# EN-C200_RA0_PWR.net
KiCad netlist of a schematic drawn in Altium Designer
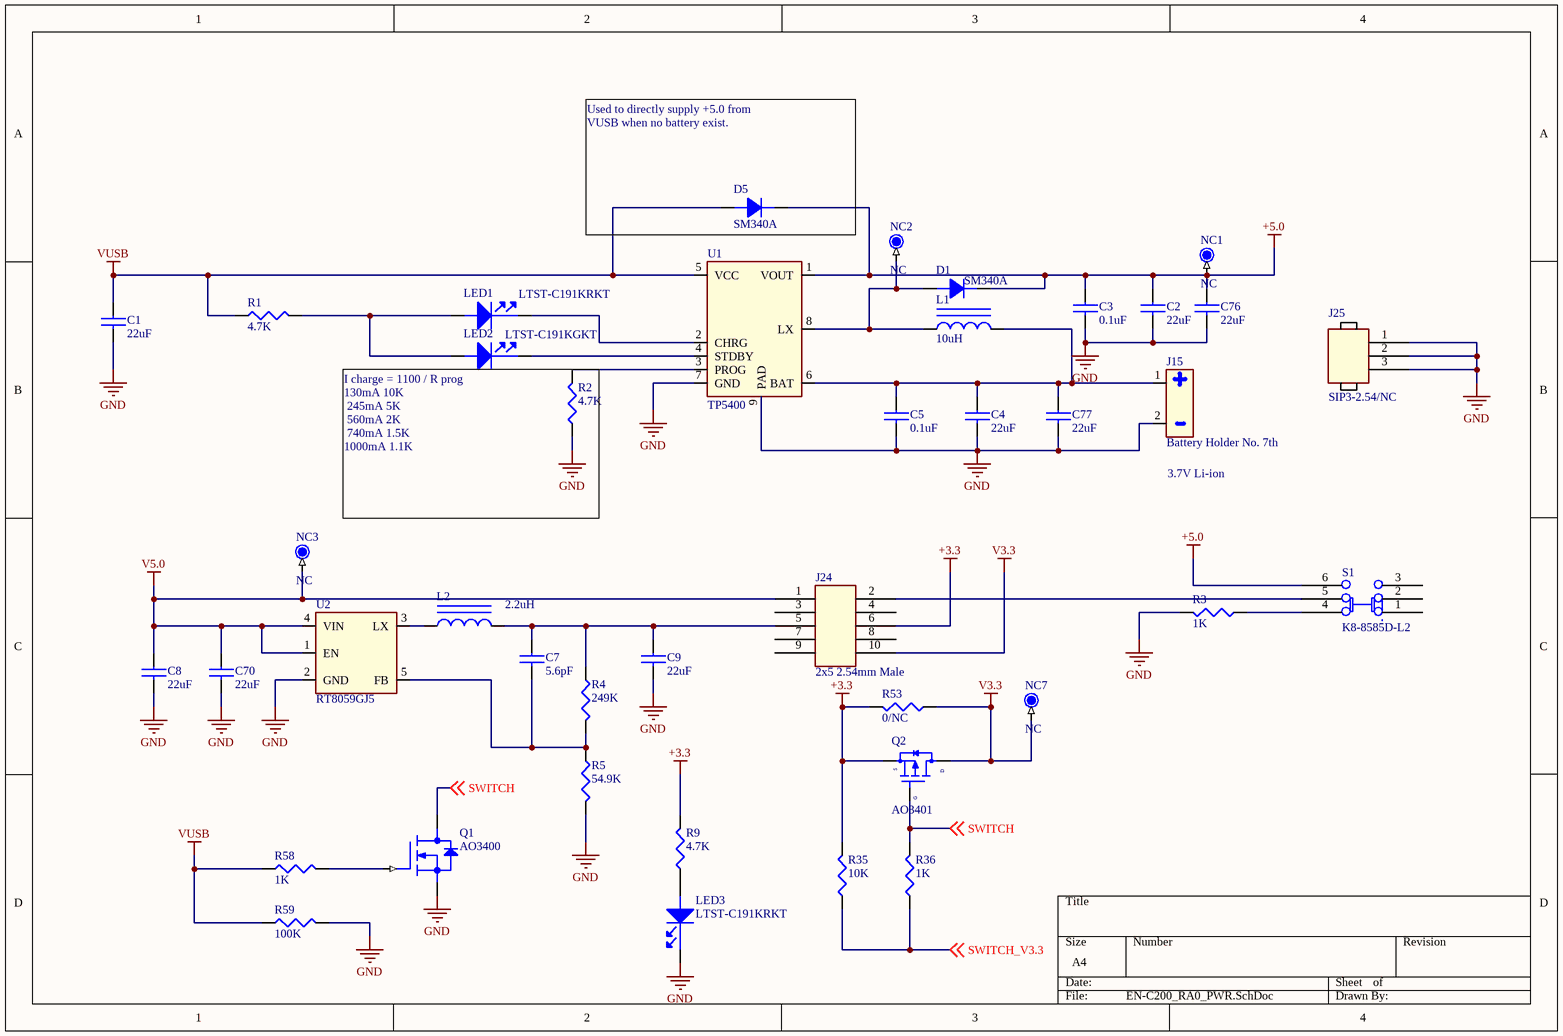
[diagram p0: EN-C200_RA0_PWR.SchDoc]

(export (version "E")
  (design (tool "Eeschema 10.0.6"))
  (components
    (comp (ref "C1") (value "22uF") (footprint "SC0805") (libsource (lib "EN-C200_RA0") (part "CAP NP")))
    (comp (ref "C2") (value "22uF") (footprint "SC0805") (libsource (lib "EN-C200_RA0") (part "CAP NP")))
    (comp (ref "C3") (value "0.1uF") (footprint "SC0603") (libsource (lib "EN-C200_RA0") (part "CAP NP")))
    (comp (ref "C4") (value "22uF") (footprint "SC0805") (libsource (lib "EN-C200_RA0") (part "CAP NP")))
    (comp (ref "C5") (value "0.1uF") (footprint "SC0603") (libsource (lib "EN-C200_RA0") (part "CAP NP")))
    (comp (ref "C7") (value "5.6pF") (footprint "SC0603") (libsource (lib "EN-C200_RA0") (part "CAP NP")))
    (comp (ref "C8") (value "22uF") (footprint "SC0805") (libsource (lib "EN-C200_RA0") (part "CAP NP")))
    (comp (ref "C9") (value "22uF") (footprint "SC0805") (libsource (lib "EN-C200_RA0") (part "CAP NP")))
    (comp (ref "C70") (value "22uF") (footprint "SC0805") (libsource (lib "EN-C200_RA0") (part "CAP NP")))
    (comp (ref "C76") (value "22uF") (footprint "SC0805") (libsource (lib "EN-C200_RA0") (part "CAP NP")))
    (comp (ref "C77") (value "22uF") (footprint "SC0805") (libsource (lib "EN-C200_RA0") (part "CAP NP")))
    (comp (ref "D1") (value "SM340A") (footprint "SD1714") (libsource (lib "EN-C200_RA0") (part "DIODE")))
    (comp (ref "D5") (value "SM340A") (footprint "SD1714") (libsource (lib "EN-C200_RA0") (part "DIODE")))
    (comp (ref "J15")
      (value "Battery Holder No. 7th")
      (footprint "BX0034")
      (libsource (lib "EN-C200_RA0") (part "BX0034"))
    )
    (comp (ref "J24")
      (value "2x5 2.54mm Male")
      (footprint "SIP-2X5P-100")
      (libsource (lib "EN-C200_RA0") (part "CON10A"))
    )
    (comp (ref "J25")
      (value "SIP3-2.54/NC")
      (footprint "SIP-3P")
      (libsource (lib "EN-C200_RA0") (part "HEADER3"))
    )
    (comp (ref "L1")
      (value "10uH")
      (footprint "SPL0505B")
      (libsource (lib "EN-C200_RA0") (part "TOROID IRON"))
    )
    (comp (ref "L2")
      (value "2.2uH")
      (footprint "SL1008")
      (libsource (lib "EN-C200_RA0") (part "TOROID IRON"))
    )
    (comp (ref "LED1")
      (value "LTST-C191KRKT")
      (footprint "HSD0603-LED")
      (libsource (lib "EN-C200_RA0") (part "LED"))
    )
    (comp (ref "LED2")
      (value "LTST-C191KGKT")
      (footprint "HSD0603-LED")
      (libsource (lib "EN-C200_RA0") (part "LED"))
    )
    (comp (ref "LED3")
      (value "LTST-C191KRKT")
      (footprint "HSD0603-LED")
      (libsource (lib "EN-C200_RA0") (part "LED"))
    )
    (comp (ref "NC1") (value "NC") (footprint "TP32-SMD") (libsource (lib "EN-C200_RA0") (part "TP")))
    (comp (ref "NC2") (value "NC") (footprint "TP32-SMD") (libsource (lib "EN-C200_RA0") (part "TP")))
    (comp (ref "NC3") (value "NC") (footprint "TP32-SMD") (libsource (lib "EN-C200_RA0") (part "TP")))
    (comp (ref "NC7") (value "NC") (footprint "TP32-SMD") (libsource (lib "EN-C200_RA0") (part "TP")))
    (comp (ref "Q1") (value "AO3400") (footprint "SOT23") (libsource (lib "EN-C200_RA0") (part "MPF6661")))
    (comp (ref "Q2") (value "AO3401") (footprint "SOT23") (libsource (lib "EN-C200_RA0") (part "A03401")))
    (comp (ref "R1") (value "4.7K") (footprint "SR0603") (libsource (lib "EN-C200_RA0") (part "RESISTOR")))
    (comp (ref "R2") (value "4.7K") (footprint "SR0603") (libsource (lib "EN-C200_RA0") (part "RESISTOR")))
    (comp (ref "R3") (value "1K") (footprint "SR0603") (libsource (lib "EN-C200_RA0") (part "RESISTOR")))
    (comp (ref "R4") (value "249K") (footprint "SR0603") (libsource (lib "EN-C200_RA0") (part "RESISTOR")))
    (comp (ref "R5") (value "54.9K") (footprint "SR0603") (libsource (lib "EN-C200_RA0") (part "RESISTOR")))
    (comp (ref "R9") (value "4.7K") (footprint "SR0603") (libsource (lib "EN-C200_RA0") (part "RESISTOR")))
    (comp (ref "R35") (value "10K") (footprint "SR0603") (libsource (lib "EN-C200_RA0") (part "RESISTOR")))
    (comp (ref "R36") (value "1K") (footprint "SR0603") (libsource (lib "EN-C200_RA0") (part "RESISTOR")))
    (comp (ref "R53") (value "0/NC") (footprint "SR0603") (libsource (lib "EN-C200_RA0") (part "RESISTOR")))
    (comp (ref "R58") (value "1K") (footprint "SR0603") (libsource (lib "EN-C200_RA0") (part "RESISTOR")))
    (comp (ref "R59") (value "100K") (footprint "SR0603") (libsource (lib "EN-C200_RA0") (part "RESISTOR")))
    (comp (ref "S1")
      (value "K8-8585D-L2")
      (footprint "SW2X3-100")
      (libsource (lib "EN-C200_RA0") (part "SW_PUSH6"))
    )
    (comp (ref "U1")
      (value "TP5400")
      (footprint "SOP8-50-150B")
      (libsource (lib "EN-C200_RA0") (part "TP5400"))
    )
    (comp (ref "U2")
      (value "RT8059GJ5")
      (footprint "SOT23-5")
      (libsource (lib "EN-C200_RA0") (part "RT8059"))
    )
  )
  (nets
    (net (code "1") (name "+3.3") (class "Default")
      (node (ref "J24") (pin "6") (pinfunction "6_6") (pintype "passive"))
      (node (ref "Q2") (pin "2") (pinfunction "S_2") (pintype "passive"))
      (node (ref "R35") (pin "2") (pinfunction "2_2") (pintype "passive"))
      (node (ref "R53") (pin "2") (pinfunction "2_2") (pintype "passive"))
      (node (ref "R9") (pin "2") (pinfunction "2_2") (pintype "passive"))
    )
    (net (code "2") (name "+5.0") (class "Default")
      (node (ref "C2") (pin "1") (pinfunction "1_1") (pintype "passive"))
      (node (ref "C3") (pin "1") (pinfunction "1_1") (pintype "passive"))
      (node (ref "C76") (pin "1") (pinfunction "1_1") (pintype "passive"))
      (node (ref "D1") (pin "2") (pinfunction "K_2") (pintype "passive"))
      (node (ref "D5") (pin "2") (pinfunction "K_2") (pintype "passive"))
      (node (ref "NC1") (pin "1") (pinfunction "1_1") (pintype "input"))
      (node (ref "S1") (pin "6") (pinfunction "6_6") (pintype "passive"))
      (node (ref "U1") (pin "1") (pinfunction "VOUT_1") (pintype "power_in"))
    )
    (net (code "3") (name "GND") (class "Default")
      (node (ref "C1") (pin "2") (pinfunction "2_2") (pintype "passive"))
      (node (ref "C2") (pin "2") (pinfunction "2_2") (pintype "passive"))
      (node (ref "C3") (pin "2") (pinfunction "2_2") (pintype "passive"))
      (node (ref "C4") (pin "2") (pinfunction "2_2") (pintype "passive"))
      (node (ref "C5") (pin "2") (pinfunction "2_2") (pintype "passive"))
      (node (ref "C70") (pin "2") (pinfunction "2_2") (pintype "passive"))
      (node (ref "C76") (pin "2") (pinfunction "2_2") (pintype "passive"))
      (node (ref "C77") (pin "2") (pinfunction "2_2") (pintype "passive"))
      (node (ref "C8") (pin "2") (pinfunction "2_2") (pintype "passive"))
      (node (ref "C9") (pin "2") (pinfunction "2_2") (pintype "passive"))
      (node (ref "J15") (pin "2") (pinfunction "2_2") (pintype "passive"))
      (node (ref "J25") (pin "1") (pinfunction "1_1") (pintype "passive"))
      (node (ref "J25") (pin "2") (pinfunction "2_2") (pintype "passive"))
      (node (ref "J25") (pin "3") (pinfunction "3_3") (pintype "passive"))
      (node (ref "LED3") (pin "2") (pinfunction "2_2") (pintype "passive"))
      (node (ref "Q1") (pin "2") (pinfunction "S_2") (pintype "passive"))
      (node (ref "R2") (pin "1") (pinfunction "1_1") (pintype "passive"))
      (node (ref "R3") (pin "2") (pinfunction "2_2") (pintype "passive"))
      (node (ref "R5") (pin "2") (pinfunction "2_2") (pintype "passive"))
      (node (ref "R59") (pin "2") (pinfunction "2_2") (pintype "passive"))
      (node (ref "U1") (pin "7") (pinfunction "GND_7") (pintype "power_in"))
      (node (ref "U1") (pin "9") (pinfunction "PAD_9") (pintype "passive"))
      (node (ref "U2") (pin "2") (pinfunction "GND_2") (pintype "power_in"))
    )
    (net (code "4") (name "Net-(C7-Pad1)") (class "Default")
      (node (ref "C7") (pin "1") (pinfunction "1_1") (pintype "passive"))
      (node (ref "C9") (pin "1") (pinfunction "1_1") (pintype "passive"))
      (node (ref "J24") (pin "5") (pinfunction "5_5") (pintype "passive"))
      (node (ref "L2") (pin "2") (pinfunction "2_2") (pintype "passive"))
      (node (ref "R4") (pin "1") (pinfunction "1_1") (pintype "passive"))
    )
    (net (code "5") (name "Net-(D1-A)") (class "Default")
      (node (ref "D1") (pin "1") (pinfunction "A_1") (pintype "passive"))
      (node (ref "L1") (pin "1") (pinfunction "1_1") (pintype "passive"))
      (node (ref "NC2") (pin "1") (pinfunction "1_1") (pintype "input"))
      (node (ref "U1") (pin "8") (pinfunction "LX_8") (pintype "passive"))
    )
    (net (code "6") (name "Net-(J24-Pad2)") (class "Default")
      (node (ref "J24") (pin "2") (pinfunction "2_2") (pintype "passive"))
      (node (ref "S1") (pin "5") (pinfunction "5_5") (pintype "passive"))
    )
    (net (code "7") (name "Net-(LED1-Pad1)") (class "Default")
      (node (ref "LED1") (pin "1") (pinfunction "1_1") (pintype "passive"))
      (node (ref "LED2") (pin "1") (pinfunction "1_1") (pintype "passive"))
      (node (ref "R1") (pin "2") (pinfunction "2_2") (pintype "passive"))
    )
    (net (code "8") (name "Net-(LED3-Pad1)") (class "Default")
      (node (ref "LED3") (pin "1") (pinfunction "1_1") (pintype "passive"))
      (node (ref "R9") (pin "1") (pinfunction "1_1") (pintype "passive"))
    )
    (net (code "9") (name "Net-(Q1-G)") (class "Default")
      (node (ref "Q1") (pin "1") (pinfunction "G_1") (pintype "input"))
      (node (ref "R58") (pin "2") (pinfunction "2_2") (pintype "passive"))
    )
    (net (code "10") (name "Net-(R3-Pad1)") (class "Default")
      (node (ref "R3") (pin "1") (pinfunction "1_1") (pintype "passive"))
      (node (ref "S1") (pin "4") (pinfunction "4_4") (pintype "passive"))
    )
    (net (code "11") (name "Net-(U1-BAT)") (class "Default")
      (node (ref "C4") (pin "1") (pinfunction "1_1") (pintype "passive"))
      (node (ref "C5") (pin "1") (pinfunction "1_1") (pintype "passive"))
      (node (ref "C77") (pin "1") (pinfunction "1_1") (pintype "passive"))
      (node (ref "J15") (pin "1") (pinfunction "1_1") (pintype "passive"))
      (node (ref "L1") (pin "2") (pinfunction "2_2") (pintype "passive"))
      (node (ref "U1") (pin "6") (pinfunction "BAT_6") (pintype "power_in"))
    )
    (net (code "12") (name "Net-(U1-CHRG)") (class "Default")
      (node (ref "LED1") (pin "2") (pinfunction "2_2") (pintype "passive"))
      (node (ref "U1") (pin "2") (pinfunction "CHRG_2") (pintype "passive"))
    )
    (net (code "13") (name "Net-(U1-PROG)") (class "Default")
      (node (ref "R2") (pin "2") (pinfunction "2_2") (pintype "passive"))
      (node (ref "U1") (pin "3") (pinfunction "PROG_3") (pintype "passive"))
    )
    (net (code "14") (name "Net-(U1-STDBY)") (class "Default")
      (node (ref "LED2") (pin "2") (pinfunction "2_2") (pintype "passive"))
      (node (ref "U1") (pin "4") (pinfunction "STDBY_4") (pintype "passive"))
    )
    (net (code "15") (name "Net-(U2-FB)") (class "Default")
      (node (ref "C7") (pin "2") (pinfunction "2_2") (pintype "passive"))
      (node (ref "R4") (pin "2") (pinfunction "2_2") (pintype "passive"))
      (node (ref "R5") (pin "1") (pinfunction "1_1") (pintype "passive"))
      (node (ref "U2") (pin "5") (pinfunction "FB_5") (pintype "passive"))
    )
    (net (code "16") (name "Net-(U2-LX)") (class "Default")
      (node (ref "L2") (pin "1") (pinfunction "1_1") (pintype "passive"))
      (node (ref "U2") (pin "3") (pinfunction "LX_3") (pintype "passive"))
    )
    (net (code "17") (name "SWITCH") (class "Default")
      (node (ref "Q1") (pin "3") (pinfunction "D_3") (pintype "passive"))
      (node (ref "Q2") (pin "1") (pinfunction "G_1") (pintype "passive"))
      (node (ref "R36") (pin "2") (pinfunction "2_2") (pintype "passive"))
    )
    (net (code "18") (name "SWITCH_V3.3") (class "Default")
      (node (ref "R35") (pin "1") (pinfunction "1_1") (pintype "passive"))
      (node (ref "R36") (pin "1") (pinfunction "1_1") (pintype "passive"))
    )
    (net (code "19") (name "V3.3") (class "Default")
      (node (ref "J24") (pin "10") (pinfunction "10_10") (pintype "passive"))
      (node (ref "NC7") (pin "1") (pinfunction "1_1") (pintype "input"))
      (node (ref "Q2") (pin "3") (pinfunction "D_3") (pintype "passive"))
      (node (ref "R53") (pin "1") (pinfunction "1_1") (pintype "passive"))
    )
    (net (code "20") (name "V5.0") (class "Default")
      (node (ref "C70") (pin "1") (pinfunction "1_1") (pintype "passive"))
      (node (ref "C8") (pin "1") (pinfunction "1_1") (pintype "passive"))
      (node (ref "J24") (pin "1") (pinfunction "1_1") (pintype "passive"))
      (node (ref "NC3") (pin "1") (pinfunction "1_1") (pintype "input"))
      (node (ref "U2") (pin "1") (pinfunction "EN_1") (pintype "passive"))
      (node (ref "U2") (pin "4") (pinfunction "VIN_4") (pintype "power_in"))
    )
    (net (code "21") (name "VUSB") (class "Default")
      (node (ref "C1") (pin "1") (pinfunction "1_1") (pintype "passive"))
      (node (ref "D5") (pin "1") (pinfunction "A_1") (pintype "passive"))
      (node (ref "R1") (pin "1") (pinfunction "1_1") (pintype "passive"))
      (node (ref "R58") (pin "1") (pinfunction "1_1") (pintype "passive"))
      (node (ref "R59") (pin "1") (pinfunction "1_1") (pintype "passive"))
      (node (ref "U1") (pin "5") (pinfunction "VCC_5") (pintype "power_in"))
    )
    (net (code "22") (name "unconnected-(J24-Pad3)") (class "Default")
      (node (ref "J24") (pin "3") (pinfunction "3_3") (pintype "passive"))
    )
    (net (code "23") (name "unconnected-(J24-Pad4)") (class "Default")
      (node (ref "J24") (pin "4") (pinfunction "4_4") (pintype "passive"))
    )
    (net (code "24") (name "unconnected-(J24-Pad7)") (class "Default")
      (node (ref "J24") (pin "7") (pinfunction "7_7") (pintype "passive"))
    )
    (net (code "25") (name "unconnected-(J24-Pad8)") (class "Default")
      (node (ref "J24") (pin "8") (pinfunction "8_8") (pintype "passive"))
    )
    (net (code "26") (name "unconnected-(J24-Pad9)") (class "Default")
      (node (ref "J24") (pin "9") (pinfunction "9_9") (pintype "passive"))
    )
    (net (code "27") (name "unconnected-(S1-Pad1)") (class "Default")
      (node (ref "S1") (pin "1") (pinfunction "1_1") (pintype "passive"))
    )
    (net (code "28") (name "unconnected-(S1-Pad2)") (class "Default")
      (node (ref "S1") (pin "2") (pinfunction "2_2") (pintype "passive"))
    )
    (net (code "29") (name "unconnected-(S1-Pad3)") (class "Default")
      (node (ref "S1") (pin "3") (pinfunction "3_3") (pintype "passive"))
    )
  )
)
